# control_board_MCU.net
KiCad netlist of a schematic drawn in EAGLE
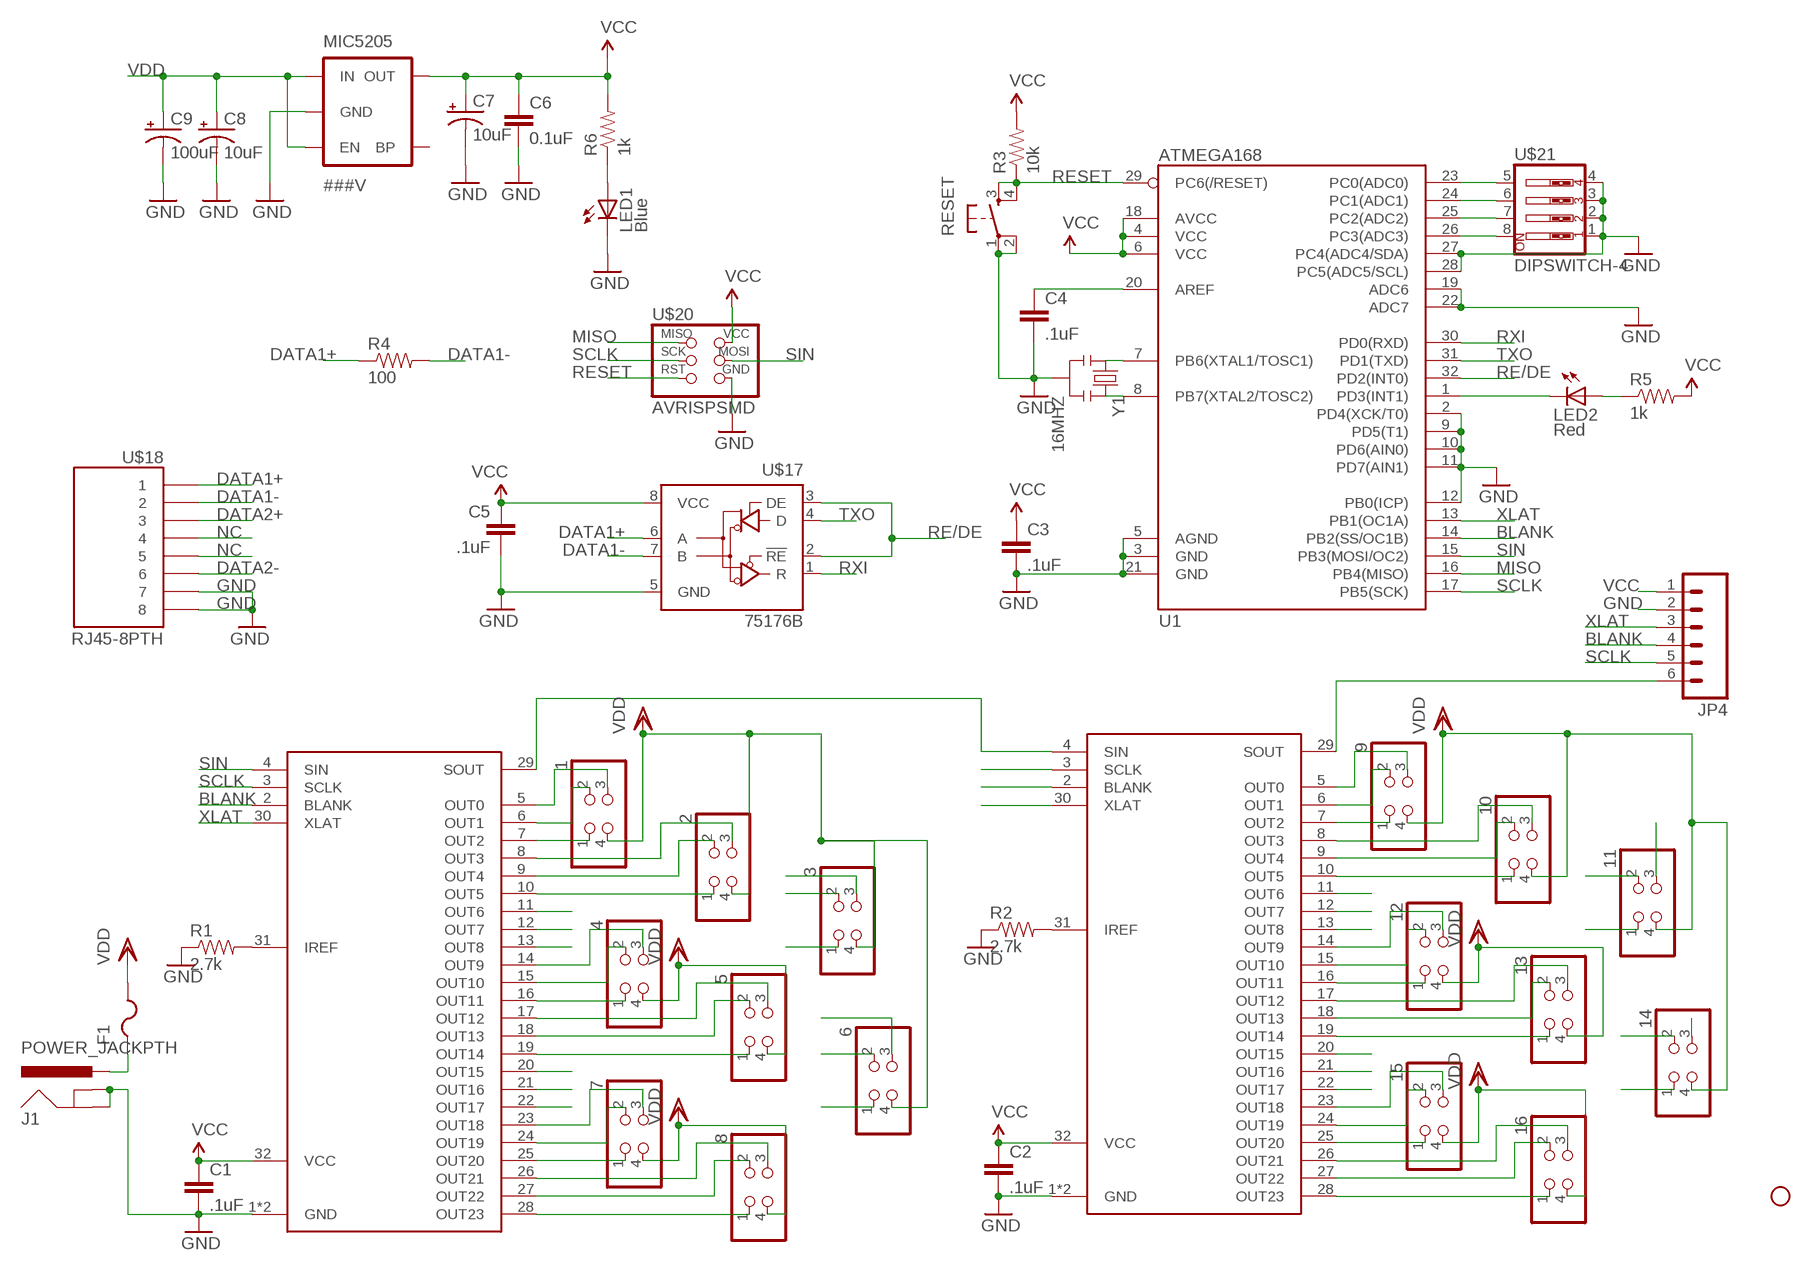
[diagram p0: schematic, sheet 1]

(export (version "E")
  (design (tool "Eeschema 10.0.6"))
  (components
    (comp (ref "1")
      (value "PINHD-2X2")
      (footprint "eagle-import:2X02")
      (libsource (lib "eagle-import") (part "PINHD-2X2"))
    )
    (comp (ref "2")
      (value "PINHD-2X2")
      (footprint "eagle-import:2X02")
      (libsource (lib "eagle-import") (part "PINHD-2X2"))
    )
    (comp (ref "3")
      (value "PINHD-2X2")
      (footprint "eagle-import:2X02")
      (libsource (lib "eagle-import") (part "PINHD-2X2"))
    )
    (comp (ref "4")
      (value "PINHD-2X2")
      (footprint "eagle-import:2X02")
      (libsource (lib "eagle-import") (part "PINHD-2X2"))
    )
    (comp (ref "5")
      (value "PINHD-2X2")
      (footprint "eagle-import:2X02")
      (libsource (lib "eagle-import") (part "PINHD-2X2"))
    )
    (comp (ref "6")
      (value "PINHD-2X2")
      (footprint "eagle-import:2X02")
      (libsource (lib "eagle-import") (part "PINHD-2X2"))
    )
    (comp (ref "7")
      (value "PINHD-2X2")
      (footprint "eagle-import:2X02")
      (libsource (lib "eagle-import") (part "PINHD-2X2"))
    )
    (comp (ref "8")
      (value "PINHD-2X2")
      (footprint "eagle-import:2X02")
      (libsource (lib "eagle-import") (part "PINHD-2X2"))
    )
    (comp (ref "9")
      (value "PINHD-2X2")
      (footprint "eagle-import:2X02")
      (libsource (lib "eagle-import") (part "PINHD-2X2"))
    )
    (comp (ref "10")
      (value "PINHD-2X2")
      (footprint "eagle-import:2X02")
      (libsource (lib "eagle-import") (part "PINHD-2X2"))
    )
    (comp (ref "11")
      (value "PINHD-2X2")
      (footprint "eagle-import:2X02")
      (libsource (lib "eagle-import") (part "PINHD-2X2"))
    )
    (comp (ref "12")
      (value "PINHD-2X2")
      (footprint "eagle-import:2X02")
      (libsource (lib "eagle-import") (part "PINHD-2X2"))
    )
    (comp (ref "13")
      (value "PINHD-2X2")
      (footprint "eagle-import:2X02")
      (libsource (lib "eagle-import") (part "PINHD-2X2"))
    )
    (comp (ref "14")
      (value "PINHD-2X2")
      (footprint "eagle-import:2X02")
      (libsource (lib "eagle-import") (part "PINHD-2X2"))
    )
    (comp (ref "15")
      (value "PINHD-2X2")
      (footprint "eagle-import:2X02")
      (libsource (lib "eagle-import") (part "PINHD-2X2"))
    )
    (comp (ref "16")
      (value "PINHD-2X2")
      (footprint "eagle-import:2X02")
      (libsource (lib "eagle-import") (part "PINHD-2X2"))
    )
    (comp (ref "C1")
      (value ".1uF")
      (footprint "eagle-import:0402-CAP")
      (libsource (lib "eagle-import") (part "CAP0402-CAP"))
    )
    (comp (ref "C2")
      (value ".1uF")
      (footprint "eagle-import:0402-CAP")
      (libsource (lib "eagle-import") (part "CAP0402-CAP"))
    )
    (comp (ref "C3")
      (value ".1uF")
      (footprint "eagle-import:0402-CAP")
      (libsource (lib "eagle-import") (part "CAP0402-CAP"))
    )
    (comp (ref "C4")
      (value ".1uF")
      (footprint "eagle-import:0402-CAP")
      (libsource (lib "eagle-import") (part "CAP0402-CAP"))
    )
    (comp (ref "C5")
      (value ".1uF")
      (footprint "eagle-import:0402-CAP")
      (libsource (lib "eagle-import") (part "CAP0402-CAP"))
    )
    (comp (ref "C6")
      (value "0.1uF")
      (footprint "eagle-import:0402-CAP")
      (libsource (lib "eagle-import") (part "CAP0402-CAP"))
    )
    (comp (ref "C7")
      (value "10uF")
      (footprint "eagle-import:EIA3216")
      (libsource (lib "eagle-import") (part "CAP_POL1206"))
    )
    (comp (ref "C8")
      (value "10uF")
      (footprint "eagle-import:EIA3216")
      (libsource (lib "eagle-import") (part "CAP_POL1206"))
    )
    (comp (ref "C9")
      (value "100uF")
      (footprint "eagle-import:PANASONIC_C")
      (libsource (lib "eagle-import") (part "CAP_POLC"))
    )
    (comp (ref "F1")
      (value "PTCFUSE-1812")
      (footprint "eagle-import:1812")
      (libsource (lib "eagle-import") (part "PTCFUSE-1812"))
    )
    (comp (ref "J1")
      (value "POWER_JACKPTH")
      (footprint "eagle-import:POWER_JACK_PTH")
      (libsource (lib "eagle-import") (part "POWER_JACKPTH"))
    )
    (comp (ref "JP4")
      (value "M06LOCK")
      (footprint "eagle-import:1X06_LOCK")
      (libsource (lib "eagle-import") (part "M06LOCK"))
    )
    (comp (ref "LED1")
      (value "Blue")
      (footprint "eagle-import:LED-0603")
      (libsource (lib "eagle-import") (part "LED0603"))
    )
    (comp (ref "LED2")
      (value "Red")
      (footprint "eagle-import:LED-0603")
      (libsource (lib "eagle-import") (part "LED0603"))
    )
    (comp (ref "MIC5205")
      (value "###V")
      (footprint "eagle-import:SOT23-5")
      (libsource (lib "eagle-import") (part "V_REG_LDOSMD"))
    )
    (comp (ref "R1")
      (value "2.7k")
      (footprint "eagle-import:0603-RES")
      (libsource (lib "eagle-import") (part "SparkFun-Resistors_RESISTOR0603-RES"))
    )
    (comp (ref "R2")
      (value "2.7k")
      (footprint "eagle-import:0603-RES")
      (libsource (lib "eagle-import") (part "SparkFun-Resistors_RESISTOR0603-RES"))
    )
    (comp (ref "R3")
      (value "10k")
      (footprint "eagle-import:0402-RES")
      (libsource (lib "eagle-import") (part "RESISTOR0402-RES"))
    )
    (comp (ref "R4")
      (value "100")
      (footprint "eagle-import:1206")
      (libsource (lib "eagle-import") (part "SparkFun-Passives_RESISTOR1206"))
    )
    (comp (ref "R5")
      (value "1k")
      (footprint "eagle-import:C0402")
      (libsource (lib "eagle-import") (part "RESISTOR0402"))
    )
    (comp (ref "R6")
      (value "1k")
      (footprint "eagle-import:C0402")
      (libsource (lib "eagle-import") (part "RESISTOR0402"))
    )
    (comp (ref "RESET")
      (value "TAC_SWITCHSMD")
      (footprint "eagle-import:TACTILE_SWITCH_SMD")
      (libsource (lib "eagle-import") (part "TAC_SWITCHSMD"))
    )
    (comp (ref "STANDOFF1")
      (value "STAND-OFF")
      (footprint "eagle-import:STAND-OFF")
      (libsource (lib "eagle-import") (part "STAND-OFF"))
    )
    (comp (ref "TLC5947")
      (value "TLC5947DAP")
      (footprint "eagle-import:DAP")
      (libsource (lib "eagle-import") (part "TLC5947DAP"))
    )
    (comp (ref "TLC5947-2")
      (value "TLC5947DAP")
      (footprint "eagle-import:DAP")
      (libsource (lib "eagle-import") (part "TLC5947DAP"))
    )
    (comp (ref "U$17")
      (value "75176B")
      (footprint "eagle-import:D_R-PDSO-G8")
      (libsource (lib "eagle-import") (part "75176B"))
    )
    (comp (ref "U$18")
      (value "RJ45-8PTH")
      (footprint "eagle-import:RJ45-8")
      (libsource (lib "eagle-import") (part "RJ45-8PTH"))
    )
    (comp (ref "U$20")
      (value "AVRISPSMD")
      (footprint "eagle-import:2X03SMD")
      (libsource (lib "eagle-import") (part "AVRISPSMD"))
    )
    (comp (ref "U$21")
      (value "DIPSWITCH-4")
      (footprint "eagle-import:DIPSWITCH-04")
      (libsource (lib "eagle-import") (part "DIPSWITCH-4"))
    )
    (comp (ref "U1")
      (value "ATMEGA168")
      (footprint "eagle-import:TQFP32-08")
      (libsource (lib "eagle-import") (part "ATMEGA168"))
    )
    (comp (ref "Y1")
      (value "16MHZ")
      (footprint "eagle-import:RESONATOR-SMD")
      (libsource (lib "eagle-import") (part "RESONATOR8MHZ"))
    )
  )
  (nets
    (net (code "1") (name "/BLANK") (class "Default")
      (node (ref "JP4") (pin "4") (pinfunction "4_4") (pintype "passive"))
      (node (ref "TLC5947") (pin "2") (pinfunction "BLANK_2") (pintype "bidirectional"))
      (node (ref "TLC5947-2") (pin "2") (pinfunction "BLANK_2") (pintype "bidirectional"))
      (node (ref "U1") (pin "14") (pinfunction "PB2(SS/OC1B)_14") (pintype "bidirectional"))
    )
    (net (code "2") (name "/DATA1+") (class "Default")
      (node (ref "R4") (pin "1") (pinfunction "1_1") (pintype "passive"))
      (node (ref "U$17") (pin "6") (pinfunction "A_6") (pintype "output"))
      (node (ref "U$18") (pin "1") (pinfunction "1_1") (pintype "bidirectional"))
    )
    (net (code "3") (name "/DATA1-") (class "Default")
      (node (ref "R4") (pin "2") (pinfunction "2_2") (pintype "passive"))
      (node (ref "U$17") (pin "7") (pinfunction "B_7") (pintype "output"))
      (node (ref "U$18") (pin "2") (pinfunction "2_2") (pintype "bidirectional"))
    )
    (net (code "4") (name "/DATA2+") (class "Default")
      (node (ref "U$18") (pin "3") (pinfunction "3_3") (pintype "bidirectional"))
    )
    (net (code "5") (name "/DATA2-") (class "Default")
      (node (ref "U$18") (pin "6") (pinfunction "6_6") (pintype "bidirectional"))
    )
    (net (code "6") (name "/MISO") (class "Default")
      (node (ref "U$20") (pin "1") (pinfunction "MISO_1") (pintype "passive"))
      (node (ref "U1") (pin "16") (pinfunction "PB4(MISO)_16") (pintype "bidirectional"))
    )
    (net (code "7") (name "/NC") (class "Default")
      (node (ref "U$18") (pin "4") (pinfunction "4_4") (pintype "bidirectional"))
      (node (ref "U$18") (pin "5") (pinfunction "5_5") (pintype "bidirectional"))
    )
    (net (code "8") (name "/OUT6") (class "Default")
      (node (ref "3") (pin "3") (pinfunction "3_3") (pintype "passive"))
      (node (ref "TLC5947") (pin "11") (pinfunction "OUT6_11") (pintype "bidirectional"))
    )
    (net (code "9") (name "/OUT7") (class "Default")
      (node (ref "3") (pin "2") (pinfunction "2_2") (pintype "passive"))
      (node (ref "TLC5947") (pin "12") (pinfunction "OUT7_12") (pintype "bidirectional"))
    )
    (net (code "10") (name "/OUT8") (class "Default")
      (node (ref "3") (pin "1") (pinfunction "1_1") (pintype "passive"))
      (node (ref "TLC5947") (pin "13") (pinfunction "OUT8_13") (pintype "bidirectional"))
    )
    (net (code "11") (name "/OUT15") (class "Default")
      (node (ref "6") (pin "3") (pinfunction "3_3") (pintype "passive"))
      (node (ref "TLC5947") (pin "20") (pinfunction "OUT15_20") (pintype "bidirectional"))
    )
    (net (code "12") (name "/OUT16") (class "Default")
      (node (ref "6") (pin "2") (pinfunction "2_2") (pintype "passive"))
      (node (ref "TLC5947") (pin "21") (pinfunction "OUT16_21") (pintype "bidirectional"))
    )
    (net (code "13") (name "/OUT17") (class "Default")
      (node (ref "6") (pin "1") (pinfunction "1_1") (pintype "passive"))
      (node (ref "TLC5947") (pin "22") (pinfunction "OUT17_22") (pintype "bidirectional"))
    )
    (net (code "14") (name "/OUT30") (class "Default")
      (node (ref "11") (pin "3") (pinfunction "3_3") (pintype "passive"))
      (node (ref "TLC5947-2") (pin "11") (pinfunction "OUT6_11") (pintype "bidirectional"))
    )
    (net (code "15") (name "/OUT31") (class "Default")
      (node (ref "11") (pin "2") (pinfunction "2_2") (pintype "passive"))
      (node (ref "TLC5947-2") (pin "12") (pinfunction "OUT7_12") (pintype "bidirectional"))
    )
    (net (code "16") (name "/OUT32") (class "Default")
      (node (ref "11") (pin "1") (pinfunction "1_1") (pintype "passive"))
      (node (ref "TLC5947-2") (pin "13") (pinfunction "OUT8_13") (pintype "bidirectional"))
    )
    (net (code "17") (name "/OUT39") (class "Default")
      (node (ref "14") (pin "3") (pinfunction "3_3") (pintype "passive"))
      (node (ref "TLC5947-2") (pin "20") (pinfunction "OUT15_20") (pintype "bidirectional"))
    )
    (net (code "18") (name "/OUT40") (class "Default")
      (node (ref "14") (pin "2") (pinfunction "2_2") (pintype "passive"))
      (node (ref "TLC5947-2") (pin "21") (pinfunction "OUT16_21") (pintype "bidirectional"))
    )
    (net (code "19") (name "/OUT41") (class "Default")
      (node (ref "14") (pin "1") (pinfunction "1_1") (pintype "passive"))
      (node (ref "TLC5947-2") (pin "22") (pinfunction "OUT17_22") (pintype "bidirectional"))
    )
    (net (code "20") (name "/RESET") (class "Default")
      (node (ref "R3") (pin "1") (pinfunction "1_1") (pintype "passive"))
      (node (ref "RESET") (pin "3") (pinfunction "3_3") (pintype "passive"))
      (node (ref "RESET") (pin "4") (pinfunction "4_4") (pintype "passive"))
      (node (ref "U$20") (pin "5") (pinfunction "RST_5") (pintype "passive"))
      (node (ref "U1") (pin "29") (pinfunction "PC6(/RESET)_29") (pintype "bidirectional"))
    )
    (net (code "21") (name "/RE{slash}DE") (class "Default")
      (node (ref "U$17") (pin "2") (pinfunction "~{RE}_2") (pintype "input"))
      (node (ref "U$17") (pin "3") (pinfunction "DE_3") (pintype "input"))
      (node (ref "U1") (pin "32") (pinfunction "PD2(INT0)_32") (pintype "bidirectional"))
    )
    (net (code "22") (name "/RXI") (class "Default")
      (node (ref "U$17") (pin "1") (pinfunction "R_1") (pintype "input"))
      (node (ref "U1") (pin "30") (pinfunction "PD0(RXD)_30") (pintype "bidirectional"))
    )
    (net (code "23") (name "/SCLK") (class "Default")
      (node (ref "JP4") (pin "5") (pinfunction "5_5") (pintype "passive"))
      (node (ref "TLC5947") (pin "3") (pinfunction "SCLK_3") (pintype "bidirectional"))
      (node (ref "TLC5947-2") (pin "3") (pinfunction "SCLK_3") (pintype "bidirectional"))
      (node (ref "U$20") (pin "3") (pinfunction "SCK_3") (pintype "passive"))
      (node (ref "U1") (pin "17") (pinfunction "PB5(SCK)_17") (pintype "bidirectional"))
    )
    (net (code "24") (name "/SIN") (class "Default")
      (node (ref "TLC5947") (pin "4") (pinfunction "SIN_4") (pintype "bidirectional"))
      (node (ref "U$20") (pin "4") (pinfunction "MOSI_4") (pintype "passive"))
      (node (ref "U1") (pin "15") (pinfunction "PB3(MOSI/OC2)_15") (pintype "bidirectional"))
    )
    (net (code "25") (name "/TXO") (class "Default")
      (node (ref "U$17") (pin "4") (pinfunction "D_4") (pintype "input"))
      (node (ref "U1") (pin "31") (pinfunction "PD1(TXD)_31") (pintype "bidirectional"))
    )
    (net (code "26") (name "/XLAT") (class "Default")
      (node (ref "JP4") (pin "3") (pinfunction "3_3") (pintype "passive"))
      (node (ref "TLC5947") (pin "30") (pinfunction "XLAT_30") (pintype "bidirectional"))
      (node (ref "TLC5947-2") (pin "30") (pinfunction "XLAT_30") (pintype "bidirectional"))
      (node (ref "U1") (pin "13") (pinfunction "PB1(OC1A)_13") (pintype "bidirectional"))
    )
    (net (code "27") (name "GND") (class "Default")
      (node (ref "C1") (pin "2") (pinfunction "2_2") (pintype "passive"))
      (node (ref "C2") (pin "2") (pinfunction "2_2") (pintype "passive"))
      (node (ref "C3") (pin "2") (pinfunction "2_2") (pintype "passive"))
      (node (ref "C4") (pin "2") (pinfunction "2_2") (pintype "passive"))
      (node (ref "C5") (pin "2") (pinfunction "2_2") (pintype "passive"))
      (node (ref "C6") (pin "2") (pinfunction "2_2") (pintype "passive"))
      (node (ref "C7") (pin "C") (pinfunction "-_C") (pintype "passive"))
      (node (ref "C8") (pin "C") (pinfunction "-_C") (pintype "passive"))
      (node (ref "C9") (pin "-") (pinfunction "-_-") (pintype "passive"))
      (node (ref "J1") (pin "GND") (pinfunction "GND_GND") (pintype "bidirectional"))
      (node (ref "J1") (pin "GNDBREAK") (pinfunction "GNDBREAK_GNDBREAK") (pintype "bidirectional"))
      (node (ref "JP4") (pin "2") (pinfunction "2_2") (pintype "passive"))
      (node (ref "LED1") (pin "C") (pinfunction "C_C") (pintype "passive"))
      (node (ref "MIC5205") (pin "2") (pinfunction "GND_2") (pintype "input"))
      (node (ref "R1") (pin "1") (pinfunction "1_1") (pintype "passive"))
      (node (ref "R2") (pin "1") (pinfunction "1_1") (pintype "passive"))
      (node (ref "RESET") (pin "1") (pinfunction "1_1") (pintype "passive"))
      (node (ref "RESET") (pin "2") (pinfunction "2_2") (pintype "passive"))
      (node (ref "TLC5947") (pin "1") (pinfunction "GND_1") (pintype "bidirectional"))
      (node (ref "TLC5947") (pin "GND") (pinfunction "GND_GND") (pintype "bidirectional"))
      (node (ref "TLC5947-2") (pin "1") (pinfunction "GND_1") (pintype "bidirectional"))
      (node (ref "TLC5947-2") (pin "GND") (pinfunction "GND_GND") (pintype "bidirectional"))
      (node (ref "U$17") (pin "5") (pinfunction "GND_5") (pintype "power_in"))
      (node (ref "U$18") (pin "7") (pinfunction "7_7") (pintype "bidirectional"))
      (node (ref "U$18") (pin "8") (pinfunction "8_8") (pintype "bidirectional"))
      (node (ref "U$20") (pin "6") (pinfunction "GND_6") (pintype "passive"))
      (node (ref "U$21") (pin "1") (pinfunction "1_1") (pintype "passive"))
      (node (ref "U$21") (pin "2") (pinfunction "2_2") (pintype "passive"))
      (node (ref "U$21") (pin "3") (pinfunction "3_3") (pintype "passive"))
      (node (ref "U$21") (pin "4") (pinfunction "4_4") (pintype "passive"))
      (node (ref "U1") (pin "10") (pinfunction "PD6(AIN0)_10") (pintype "bidirectional"))
      (node (ref "U1") (pin "11") (pinfunction "PD7(AIN1)_11") (pintype "bidirectional"))
      (node (ref "U1") (pin "12") (pinfunction "PB0(ICP)_12") (pintype "bidirectional"))
      (node (ref "U1") (pin "19") (pinfunction "ADC6_19") (pintype "bidirectional"))
      (node (ref "U1") (pin "2") (pinfunction "PD4(XCK/T0)_2") (pintype "bidirectional"))
      (node (ref "U1") (pin "21") (pinfunction "GND_21") (pintype "bidirectional"))
      (node (ref "U1") (pin "22") (pinfunction "ADC7_22") (pintype "bidirectional"))
      (node (ref "U1") (pin "27") (pinfunction "PC4(ADC4/SDA)_27") (pintype "bidirectional"))
      (node (ref "U1") (pin "28") (pinfunction "PC5(ADC5/SCL)_28") (pintype "bidirectional"))
      (node (ref "U1") (pin "3") (pinfunction "GND_3") (pintype "bidirectional"))
      (node (ref "U1") (pin "5") (pinfunction "AGND_5") (pintype "bidirectional"))
      (node (ref "U1") (pin "9") (pinfunction "PD5(T1)_9") (pintype "bidirectional"))
      (node (ref "Y1") (pin "2") (pinfunction "2_2") (pintype "passive"))
    )
    (net (code "28") (name "Net-(F1-Pad1)") (class "Default")
      (node (ref "F1") (pin "1") (pinfunction "1_1") (pintype "passive"))
      (node (ref "J1") (pin "PWR") (pinfunction "PWR_PWR") (pintype "bidirectional"))
    )
    (net (code "29") (name "Net-(LED1-PadA)") (class "Default")
      (node (ref "LED1") (pin "A") (pinfunction "A_A") (pintype "passive"))
      (node (ref "R6") (pin "1") (pinfunction "1_1") (pintype "passive"))
    )
    (net (code "30") (name "Net-(LED2-PadA)") (class "Default")
      (node (ref "LED2") (pin "A") (pinfunction "A_A") (pintype "passive"))
      (node (ref "R5") (pin "1") (pinfunction "1_1") (pintype "passive"))
    )
    (net (code "31") (name "Net-(TLC5947-2-IREF)") (class "Default")
      (node (ref "R2") (pin "2") (pinfunction "2_2") (pintype "passive"))
      (node (ref "TLC5947-2") (pin "31") (pinfunction "IREF_31") (pintype "bidirectional"))
    )
    (net (code "32") (name "Net-(TLC5947-2-OUT0)") (class "Default")
      (node (ref "9") (pin "3") (pinfunction "3_3") (pintype "passive"))
      (node (ref "TLC5947-2") (pin "5") (pinfunction "OUT0_5") (pintype "bidirectional"))
    )
    (net (code "33") (name "Net-(TLC5947-2-OUT1)") (class "Default")
      (node (ref "9") (pin "2") (pinfunction "2_2") (pintype "passive"))
      (node (ref "TLC5947-2") (pin "6") (pinfunction "OUT1_6") (pintype "bidirectional"))
    )
    (net (code "34") (name "Net-(TLC5947-2-OUT2)") (class "Default")
      (node (ref "9") (pin "1") (pinfunction "1_1") (pintype "passive"))
      (node (ref "TLC5947-2") (pin "7") (pinfunction "OUT2_7") (pintype "bidirectional"))
    )
    (net (code "35") (name "Net-(TLC5947-2-OUT3)") (class "Default")
      (node (ref "10") (pin "3") (pinfunction "3_3") (pintype "passive"))
      (node (ref "TLC5947-2") (pin "8") (pinfunction "OUT3_8") (pintype "bidirectional"))
    )
    (net (code "36") (name "Net-(TLC5947-2-OUT4)") (class "Default")
      (node (ref "10") (pin "2") (pinfunction "2_2") (pintype "passive"))
      (node (ref "TLC5947-2") (pin "9") (pinfunction "OUT4_9") (pintype "bidirectional"))
    )
    (net (code "37") (name "Net-(TLC5947-2-OUT5)") (class "Default")
      (node (ref "10") (pin "1") (pinfunction "1_1") (pintype "passive"))
      (node (ref "TLC5947-2") (pin "10") (pinfunction "OUT5_10") (pintype "bidirectional"))
    )
    (net (code "38") (name "Net-(TLC5947-2-OUT9)") (class "Default")
      (node (ref "12") (pin "3") (pinfunction "3_3") (pintype "passive"))
      (node (ref "TLC5947-2") (pin "14") (pinfunction "OUT9_14") (pintype "bidirectional"))
    )
    (net (code "39") (name "Net-(TLC5947-2-OUT10)") (class "Default")
      (node (ref "12") (pin "2") (pinfunction "2_2") (pintype "passive"))
      (node (ref "TLC5947-2") (pin "15") (pinfunction "OUT10_15") (pintype "bidirectional"))
    )
    (net (code "40") (name "Net-(TLC5947-2-OUT11)") (class "Default")
      (node (ref "12") (pin "1") (pinfunction "1_1") (pintype "passive"))
      (node (ref "TLC5947-2") (pin "16") (pinfunction "OUT11_16") (pintype "bidirectional"))
    )
    (net (code "41") (name "Net-(TLC5947-2-OUT12)") (class "Default")
      (node (ref "13") (pin "3") (pinfunction "3_3") (pintype "passive"))
      (node (ref "TLC5947-2") (pin "17") (pinfunction "OUT12_17") (pintype "bidirectional"))
    )
    (net (code "42") (name "Net-(TLC5947-2-OUT13)") (class "Default")
      (node (ref "13") (pin "2") (pinfunction "2_2") (pintype "passive"))
      (node (ref "TLC5947-2") (pin "18") (pinfunction "OUT13_18") (pintype "bidirectional"))
    )
    (net (code "43") (name "Net-(TLC5947-2-OUT14)") (class "Default")
      (node (ref "13") (pin "1") (pinfunction "1_1") (pintype "passive"))
      (node (ref "TLC5947-2") (pin "19") (pinfunction "OUT14_19") (pintype "bidirectional"))
    )
    (net (code "44") (name "Net-(TLC5947-2-OUT18)") (class "Default")
      (node (ref "15") (pin "3") (pinfunction "3_3") (pintype "passive"))
      (node (ref "TLC5947-2") (pin "23") (pinfunction "OUT18_23") (pintype "bidirectional"))
    )
    (net (code "45") (name "Net-(TLC5947-2-OUT19)") (class "Default")
      (node (ref "15") (pin "2") (pinfunction "2_2") (pintype "passive"))
      (node (ref "TLC5947-2") (pin "24") (pinfunction "OUT19_24") (pintype "bidirectional"))
    )
    (net (code "46") (name "Net-(TLC5947-2-OUT20)") (class "Default")
      (node (ref "15") (pin "1") (pinfunction "1_1") (pintype "passive"))
      (node (ref "TLC5947-2") (pin "25") (pinfunction "OUT20_25") (pintype "bidirectional"))
    )
    (net (code "47") (name "Net-(TLC5947-2-OUT21)") (class "Default")
      (node (ref "16") (pin "3") (pinfunction "3_3") (pintype "passive"))
      (node (ref "TLC5947-2") (pin "26") (pinfunction "OUT21_26") (pintype "bidirectional"))
    )
    (net (code "48") (name "Net-(TLC5947-2-OUT22)") (class "Default")
      (node (ref "16") (pin "2") (pinfunction "2_2") (pintype "passive"))
      (node (ref "TLC5947-2") (pin "27") (pinfunction "OUT22_27") (pintype "bidirectional"))
    )
    (net (code "49") (name "Net-(TLC5947-2-OUT23)") (class "Default")
      (node (ref "16") (pin "1") (pinfunction "1_1") (pintype "passive"))
      (node (ref "TLC5947-2") (pin "28") (pinfunction "OUT23_28") (pintype "bidirectional"))
    )
    (net (code "50") (name "Net-(TLC5947-2-SIN)") (class "Default")
      (node (ref "TLC5947") (pin "29") (pinfunction "SOUT_29") (pintype "bidirectional"))
      (node (ref "TLC5947-2") (pin "4") (pinfunction "SIN_4") (pintype "bidirectional"))
    )
    (net (code "51") (name "Net-(TLC5947-2-SOUT)") (class "Default")
      (node (ref "JP4") (pin "6") (pinfunction "6_6") (pintype "passive"))
      (node (ref "TLC5947-2") (pin "29") (pinfunction "SOUT_29") (pintype "bidirectional"))
    )
    (net (code "52") (name "Net-(TLC5947-IREF)") (class "Default")
      (node (ref "R1") (pin "2") (pinfunction "2_2") (pintype "passive"))
      (node (ref "TLC5947") (pin "31") (pinfunction "IREF_31") (pintype "bidirectional"))
    )
    (net (code "53") (name "Net-(TLC5947-OUT0)") (class "Default")
      (node (ref "1") (pin "3") (pinfunction "3_3") (pintype "passive"))
      (node (ref "TLC5947") (pin "5") (pinfunction "OUT0_5") (pintype "bidirectional"))
    )
    (net (code "54") (name "Net-(TLC5947-OUT1)") (class "Default")
      (node (ref "1") (pin "2") (pinfunction "2_2") (pintype "passive"))
      (node (ref "TLC5947") (pin "6") (pinfunction "OUT1_6") (pintype "bidirectional"))
    )
    (net (code "55") (name "Net-(TLC5947-OUT2)") (class "Default")
      (node (ref "1") (pin "1") (pinfunction "1_1") (pintype "passive"))
      (node (ref "TLC5947") (pin "7") (pinfunction "OUT2_7") (pintype "bidirectional"))
    )
    (net (code "56") (name "Net-(TLC5947-OUT3)") (class "Default")
      (node (ref "2") (pin "3") (pinfunction "3_3") (pintype "passive"))
      (node (ref "TLC5947") (pin "8") (pinfunction "OUT3_8") (pintype "bidirectional"))
    )
    (net (code "57") (name "Net-(TLC5947-OUT4)") (class "Default")
      (node (ref "2") (pin "2") (pinfunction "2_2") (pintype "passive"))
      (node (ref "TLC5947") (pin "9") (pinfunction "OUT4_9") (pintype "bidirectional"))
    )
    (net (code "58") (name "Net-(TLC5947-OUT5)") (class "Default")
      (node (ref "2") (pin "1") (pinfunction "1_1") (pintype "passive"))
      (node (ref "TLC5947") (pin "10") (pinfunction "OUT5_10") (pintype "bidirectional"))
    )
    (net (code "59") (name "Net-(TLC5947-OUT9)") (class "Default")
      (node (ref "4") (pin "3") (pinfunction "3_3") (pintype "passive"))
      (node (ref "TLC5947") (pin "14") (pinfunction "OUT9_14") (pintype "bidirectional"))
    )
    (net (code "60") (name "Net-(TLC5947-OUT10)") (class "Default")
      (node (ref "4") (pin "2") (pinfunction "2_2") (pintype "passive"))
      (node (ref "TLC5947") (pin "15") (pinfunction "OUT10_15") (pintype "bidirectional"))
    )
    (net (code "61") (name "Net-(TLC5947-OUT11)") (class "Default")
      (node (ref "4") (pin "1") (pinfunction "1_1") (pintype "passive"))
      (node (ref "TLC5947") (pin "16") (pinfunction "OUT11_16") (pintype "bidirectional"))
    )
    (net (code "62") (name "Net-(TLC5947-OUT12)") (class "Default")
      (node (ref "5") (pin "3") (pinfunction "3_3") (pintype "passive"))
      (node (ref "TLC5947") (pin "17") (pinfunction "OUT12_17") (pintype "bidirectional"))
    )
    (net (code "63") (name "Net-(TLC5947-OUT13)") (class "Default")
      (node (ref "5") (pin "2") (pinfunction "2_2") (pintype "passive"))
      (node (ref "TLC5947") (pin "18") (pinfunction "OUT13_18") (pintype "bidirectional"))
    )
    (net (code "64") (name "Net-(TLC5947-OUT14)") (class "Default")
      (node (ref "5") (pin "1") (pinfunction "1_1") (pintype "passive"))
      (node (ref "TLC5947") (pin "19") (pinfunction "OUT14_19") (pintype "bidirectional"))
    )
    (net (code "65") (name "Net-(TLC5947-OUT18)") (class "Default")
      (node (ref "7") (pin "3") (pinfunction "3_3") (pintype "passive"))
      (node (ref "TLC5947") (pin "23") (pinfunction "OUT18_23") (pintype "bidirectional"))
    )
    (net (code "66") (name "Net-(TLC5947-OUT19)") (class "Default")
      (node (ref "7") (pin "2") (pinfunction "2_2") (pintype "passive"))
      (node (ref "TLC5947") (pin "24") (pinfunction "OUT19_24") (pintype "bidirectional"))
    )
    (net (code "67") (name "Net-(TLC5947-OUT20)") (class "Default")
      (node (ref "7") (pin "1") (pinfunction "1_1") (pintype "passive"))
      (node (ref "TLC5947") (pin "25") (pinfunction "OUT20_25") (pintype "bidirectional"))
    )
    (net (code "68") (name "Net-(TLC5947-OUT21)") (class "Default")
      (node (ref "8") (pin "3") (pinfunction "3_3") (pintype "passive"))
      (node (ref "TLC5947") (pin "26") (pinfunction "OUT21_26") (pintype "bidirectional"))
    )
    (net (code "69") (name "Net-(TLC5947-OUT22)") (class "Default")
      (node (ref "8") (pin "2") (pinfunction "2_2") (pintype "passive"))
      (node (ref "TLC5947") (pin "27") (pinfunction "OUT22_27") (pintype "bidirectional"))
    )
    (net (code "70") (name "Net-(TLC5947-OUT23)") (class "Default")
      (node (ref "8") (pin "1") (pinfunction "1_1") (pintype "passive"))
      (node (ref "TLC5947") (pin "28") (pinfunction "OUT23_28") (pintype "bidirectional"))
    )
    (net (code "71") (name "Net-(U1-AREF)") (class "Default")
      (node (ref "C4") (pin "1") (pinfunction "1_1") (pintype "passive"))
      (node (ref "U1") (pin "20") (pinfunction "AREF_20") (pintype "bidirectional"))
    )
    (net (code "72") (name "Net-(U1-PB6(XTAL1{slash}TOSC1))") (class "Default")
      (node (ref "U1") (pin "7") (pinfunction "PB6(XTAL1/TOSC1)_7") (pintype "bidirectional"))
      (node (ref "Y1") (pin "1") (pinfunction "1_1") (pintype "passive"))
    )
    (net (code "73") (name "Net-(U1-PB7(XTAL2{slash}TOSC2))") (class "Default")
      (node (ref "U1") (pin "8") (pinfunction "PB7(XTAL2/TOSC2)_8") (pintype "bidirectional"))
      (node (ref "Y1") (pin "3") (pinfunction "3_3") (pintype "passive"))
    )
    (net (code "74") (name "Net-(U1-PC0(ADC0))") (class "Default")
      (node (ref "U$21") (pin "5") (pinfunction "5_5") (pintype "passive"))
      (node (ref "U1") (pin "23") (pinfunction "PC0(ADC0)_23") (pintype "bidirectional"))
    )
    (net (code "75") (name "Net-(U1-PC1(ADC1))") (class "Default")
      (node (ref "U$21") (pin "6") (pinfunction "6_6") (pintype "passive"))
      (node (ref "U1") (pin "24") (pinfunction "PC1(ADC1)_24") (pintype "bidirectional"))
    )
    (net (code "76") (name "Net-(U1-PC2(ADC2))") (class "Default")
      (node (ref "U$21") (pin "7") (pinfunction "7_7") (pintype "passive"))
      (node (ref "U1") (pin "25") (pinfunction "PC2(ADC2)_25") (pintype "bidirectional"))
    )
    (net (code "77") (name "Net-(U1-PC3(ADC3))") (class "Default")
      (node (ref "U$21") (pin "8") (pinfunction "8_8") (pintype "passive"))
      (node (ref "U1") (pin "26") (pinfunction "PC3(ADC3)_26") (pintype "bidirectional"))
    )
    (net (code "78") (name "Net-(U1-PD3(INT1))") (class "Default")
      (node (ref "LED2") (pin "C") (pinfunction "C_C") (pintype "passive"))
      (node (ref "U1") (pin "1") (pinfunction "PD3(INT1)_1") (pintype "bidirectional"))
    )
    (net (code "79") (name "VCC") (class "Default")
      (node (ref "C1") (pin "1") (pinfunction "1_1") (pintype "passive"))
      (node (ref "C2") (pin "1") (pinfunction "1_1") (pintype "passive"))
      (node (ref "C3") (pin "1") (pinfunction "1_1") (pintype "passive"))
      (node (ref "C5") (pin "1") (pinfunction "1_1") (pintype "passive"))
      (node (ref "C6") (pin "1") (pinfunction "1_1") (pintype "passive"))
      (node (ref "C7") (pin "A") (pinfunction "+_A") (pintype "passive"))
      (node (ref "JP4") (pin "1") (pinfunction "1_1") (pintype "passive"))
      (node (ref "MIC5205") (pin "5") (pinfunction "OUT_5") (pintype "passive"))
      (node (ref "R3") (pin "2") (pinfunction "2_2") (pintype "passive"))
      (node (ref "R5") (pin "2") (pinfunction "2_2") (pintype "passive"))
      (node (ref "R6") (pin "2") (pinfunction "2_2") (pintype "passive"))
      (node (ref "TLC5947") (pin "32") (pinfunction "VCC_32") (pintype "bidirectional"))
      (node (ref "TLC5947-2") (pin "32") (pinfunction "VCC_32") (pintype "bidirectional"))
      (node (ref "U$17") (pin "8") (pinfunction "VCC_8") (pintype "power_in"))
      (node (ref "U$20") (pin "2") (pinfunction "VCC_2") (pintype "passive"))
      (node (ref "U1") (pin "18") (pinfunction "AVCC_18") (pintype "bidirectional"))
      (node (ref "U1") (pin "4") (pinfunction "VCC_4") (pintype "bidirectional"))
      (node (ref "U1") (pin "6") (pinfunction "VCC_6") (pintype "bidirectional"))
    )
    (net (code "80") (name "VDD") (class "Default")
      (node (ref "1") (pin "4") (pinfunction "4_4") (pintype "passive"))
      (node (ref "10") (pin "4") (pinfunction "4_4") (pintype "passive"))
      (node (ref "11") (pin "4") (pinfunction "4_4") (pintype "passive"))
      (node (ref "12") (pin "4") (pinfunction "4_4") (pintype "passive"))
      (node (ref "13") (pin "4") (pinfunction "4_4") (pintype "passive"))
      (node (ref "14") (pin "4") (pinfunction "4_4") (pintype "passive"))
      (node (ref "15") (pin "4") (pinfunction "4_4") (pintype "passive"))
      (node (ref "16") (pin "4") (pinfunction "4_4") (pintype "passive"))
      (node (ref "2") (pin "4") (pinfunction "4_4") (pintype "passive"))
      (node (ref "3") (pin "4") (pinfunction "4_4") (pintype "passive"))
      (node (ref "4") (pin "4") (pinfunction "4_4") (pintype "passive"))
      (node (ref "5") (pin "4") (pinfunction "4_4") (pintype "passive"))
      (node (ref "6") (pin "4") (pinfunction "4_4") (pintype "passive"))
      (node (ref "7") (pin "4") (pinfunction "4_4") (pintype "passive"))
      (node (ref "8") (pin "4") (pinfunction "4_4") (pintype "passive"))
      (node (ref "9") (pin "4") (pinfunction "4_4") (pintype "passive"))
      (node (ref "C8") (pin "A") (pinfunction "+_A") (pintype "passive"))
      (node (ref "C9") (pin "+") (pinfunction "+_+") (pintype "passive"))
      (node (ref "F1") (pin "2") (pinfunction "2_2") (pintype "passive"))
      (node (ref "MIC5205") (pin "1") (pinfunction "IN_1") (pintype "input"))
      (node (ref "MIC5205") (pin "3") (pinfunction "EN_3") (pintype "input"))
    )
    (net (code "81") (name "unconnected-(MIC5205-BP-Pad4)") (class "Default")
      (node (ref "MIC5205") (pin "4") (pinfunction "BP_4") (pintype "input"))
    )
  )
)
